# DA-15_DB-9_DE-15.net
KiCad netlist of a schematic drawn in EAGLE
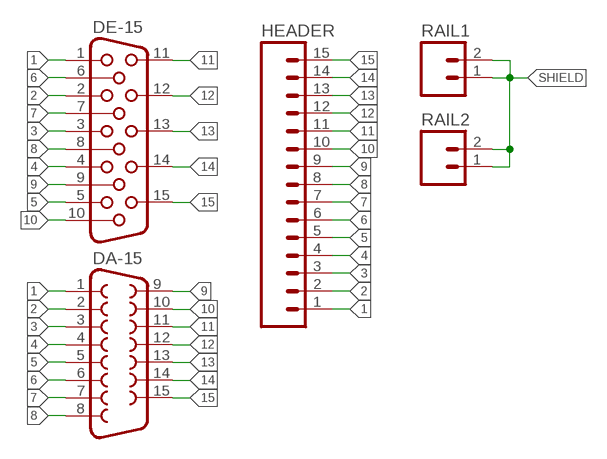
[diagram p0: schematic, sheet 1]

(export (version "E")
  (design (tool "Eeschema 10.0.6"))
  (components
    (comp (ref "DA-15")
      (value "F15VB")
      (footprint "eagle-import:F15VB")
      (libsource (lib "eagle-import") (part "F15VB"))
    )
    (comp (ref "DE-15")
      (value "HF15H")
      (footprint "eagle-import:HDF15H")
      (libsource (lib "eagle-import") (part "HF15H"))
    )
    (comp (ref "HEADER")
      (value "M15")
      (footprint "eagle-import:1X15")
      (libsource (lib "eagle-import") (part "M15"))
    )
    (comp (ref "RAIL1")
      (value "M02PTH")
      (footprint "eagle-import:1X02")
      (libsource (lib "eagle-import") (part "M02PTH"))
    )
    (comp (ref "RAIL2")
      (value "M02PTH")
      (footprint "eagle-import:1X02")
      (libsource (lib "eagle-import") (part "M02PTH"))
    )
  )
  (nets
    (net (code "1") (name "1") (class "Default")
      (node (ref "DA-15") (pin "1") (pinfunction "1_1") (pintype "passive"))
      (node (ref "DE-15") (pin "1") (pinfunction "1_1") (pintype "passive"))
      (node (ref "HEADER") (pin "1") (pinfunction "1_1") (pintype "passive"))
    )
    (net (code "2") (name "2") (class "Default")
      (node (ref "DA-15") (pin "2") (pinfunction "2_2") (pintype "passive"))
      (node (ref "DE-15") (pin "2") (pinfunction "2_2") (pintype "passive"))
      (node (ref "HEADER") (pin "2") (pinfunction "2_2") (pintype "passive"))
    )
    (net (code "3") (name "3") (class "Default")
      (node (ref "DA-15") (pin "3") (pinfunction "3_3") (pintype "passive"))
      (node (ref "DE-15") (pin "3") (pinfunction "3_3") (pintype "passive"))
      (node (ref "HEADER") (pin "3") (pinfunction "3_3") (pintype "passive"))
    )
    (net (code "4") (name "4") (class "Default")
      (node (ref "DA-15") (pin "4") (pinfunction "4_4") (pintype "passive"))
      (node (ref "DE-15") (pin "4") (pinfunction "4_4") (pintype "passive"))
      (node (ref "HEADER") (pin "4") (pinfunction "4_4") (pintype "passive"))
    )
    (net (code "5") (name "5") (class "Default")
      (node (ref "DA-15") (pin "5") (pinfunction "5_5") (pintype "passive"))
      (node (ref "DE-15") (pin "5") (pinfunction "5_5") (pintype "passive"))
      (node (ref "HEADER") (pin "5") (pinfunction "5_5") (pintype "passive"))
    )
    (net (code "6") (name "6") (class "Default")
      (node (ref "DA-15") (pin "6") (pinfunction "6_6") (pintype "passive"))
      (node (ref "DE-15") (pin "6") (pinfunction "6_6") (pintype "passive"))
      (node (ref "HEADER") (pin "6") (pinfunction "6_6") (pintype "passive"))
    )
    (net (code "7") (name "7") (class "Default")
      (node (ref "DA-15") (pin "7") (pinfunction "7_7") (pintype "passive"))
      (node (ref "DE-15") (pin "7") (pinfunction "7_7") (pintype "passive"))
      (node (ref "HEADER") (pin "7") (pinfunction "7_7") (pintype "passive"))
    )
    (net (code "8") (name "8") (class "Default")
      (node (ref "DA-15") (pin "8") (pinfunction "8_8") (pintype "passive"))
      (node (ref "DE-15") (pin "8") (pinfunction "8_8") (pintype "passive"))
      (node (ref "HEADER") (pin "8") (pinfunction "8_8") (pintype "passive"))
    )
    (net (code "9") (name "9") (class "Default")
      (node (ref "DA-15") (pin "9") (pinfunction "9_9") (pintype "passive"))
      (node (ref "DE-15") (pin "9") (pinfunction "9_9") (pintype "passive"))
      (node (ref "HEADER") (pin "9") (pinfunction "9_9") (pintype "passive"))
    )
    (net (code "10") (name "10") (class "Default")
      (node (ref "DA-15") (pin "10") (pinfunction "10_10") (pintype "passive"))
      (node (ref "DE-15") (pin "10") (pinfunction "10_10") (pintype "passive"))
      (node (ref "HEADER") (pin "10") (pinfunction "10_10") (pintype "passive"))
    )
    (net (code "11") (name "11") (class "Default")
      (node (ref "DA-15") (pin "11") (pinfunction "11_11") (pintype "passive"))
      (node (ref "DE-15") (pin "11") (pinfunction "11_11") (pintype "passive"))
      (node (ref "HEADER") (pin "11") (pinfunction "11_11") (pintype "passive"))
    )
    (net (code "12") (name "12") (class "Default")
      (node (ref "DA-15") (pin "12") (pinfunction "12_12") (pintype "passive"))
      (node (ref "DE-15") (pin "12") (pinfunction "12_12") (pintype "passive"))
      (node (ref "HEADER") (pin "12") (pinfunction "12_12") (pintype "passive"))
    )
    (net (code "13") (name "13") (class "Default")
      (node (ref "DA-15") (pin "13") (pinfunction "13_13") (pintype "passive"))
      (node (ref "DE-15") (pin "13") (pinfunction "13_13") (pintype "passive"))
      (node (ref "HEADER") (pin "13") (pinfunction "13_13") (pintype "passive"))
    )
    (net (code "14") (name "14") (class "Default")
      (node (ref "DA-15") (pin "14") (pinfunction "14_14") (pintype "passive"))
      (node (ref "DE-15") (pin "14") (pinfunction "14_14") (pintype "passive"))
      (node (ref "HEADER") (pin "14") (pinfunction "14_14") (pintype "passive"))
    )
    (net (code "15") (name "15") (class "Default")
      (node (ref "DA-15") (pin "15") (pinfunction "15_15") (pintype "passive"))
      (node (ref "DE-15") (pin "15") (pinfunction "15_15") (pintype "passive"))
      (node (ref "HEADER") (pin "15") (pinfunction "15_15") (pintype "passive"))
    )
    (net (code "16") (name "SHIELD") (class "Default")
      (node (ref "RAIL1") (pin "1") (pinfunction "1_1") (pintype "passive"))
      (node (ref "RAIL1") (pin "2") (pinfunction "2_2") (pintype "passive"))
      (node (ref "RAIL2") (pin "1") (pinfunction "1_1") (pintype "passive"))
      (node (ref "RAIL2") (pin "2") (pinfunction "2_2") (pintype "passive"))
    )
  )
)
